# monoblink_wifi.net
KiCad netlist of a schematic drawn in EAGLE
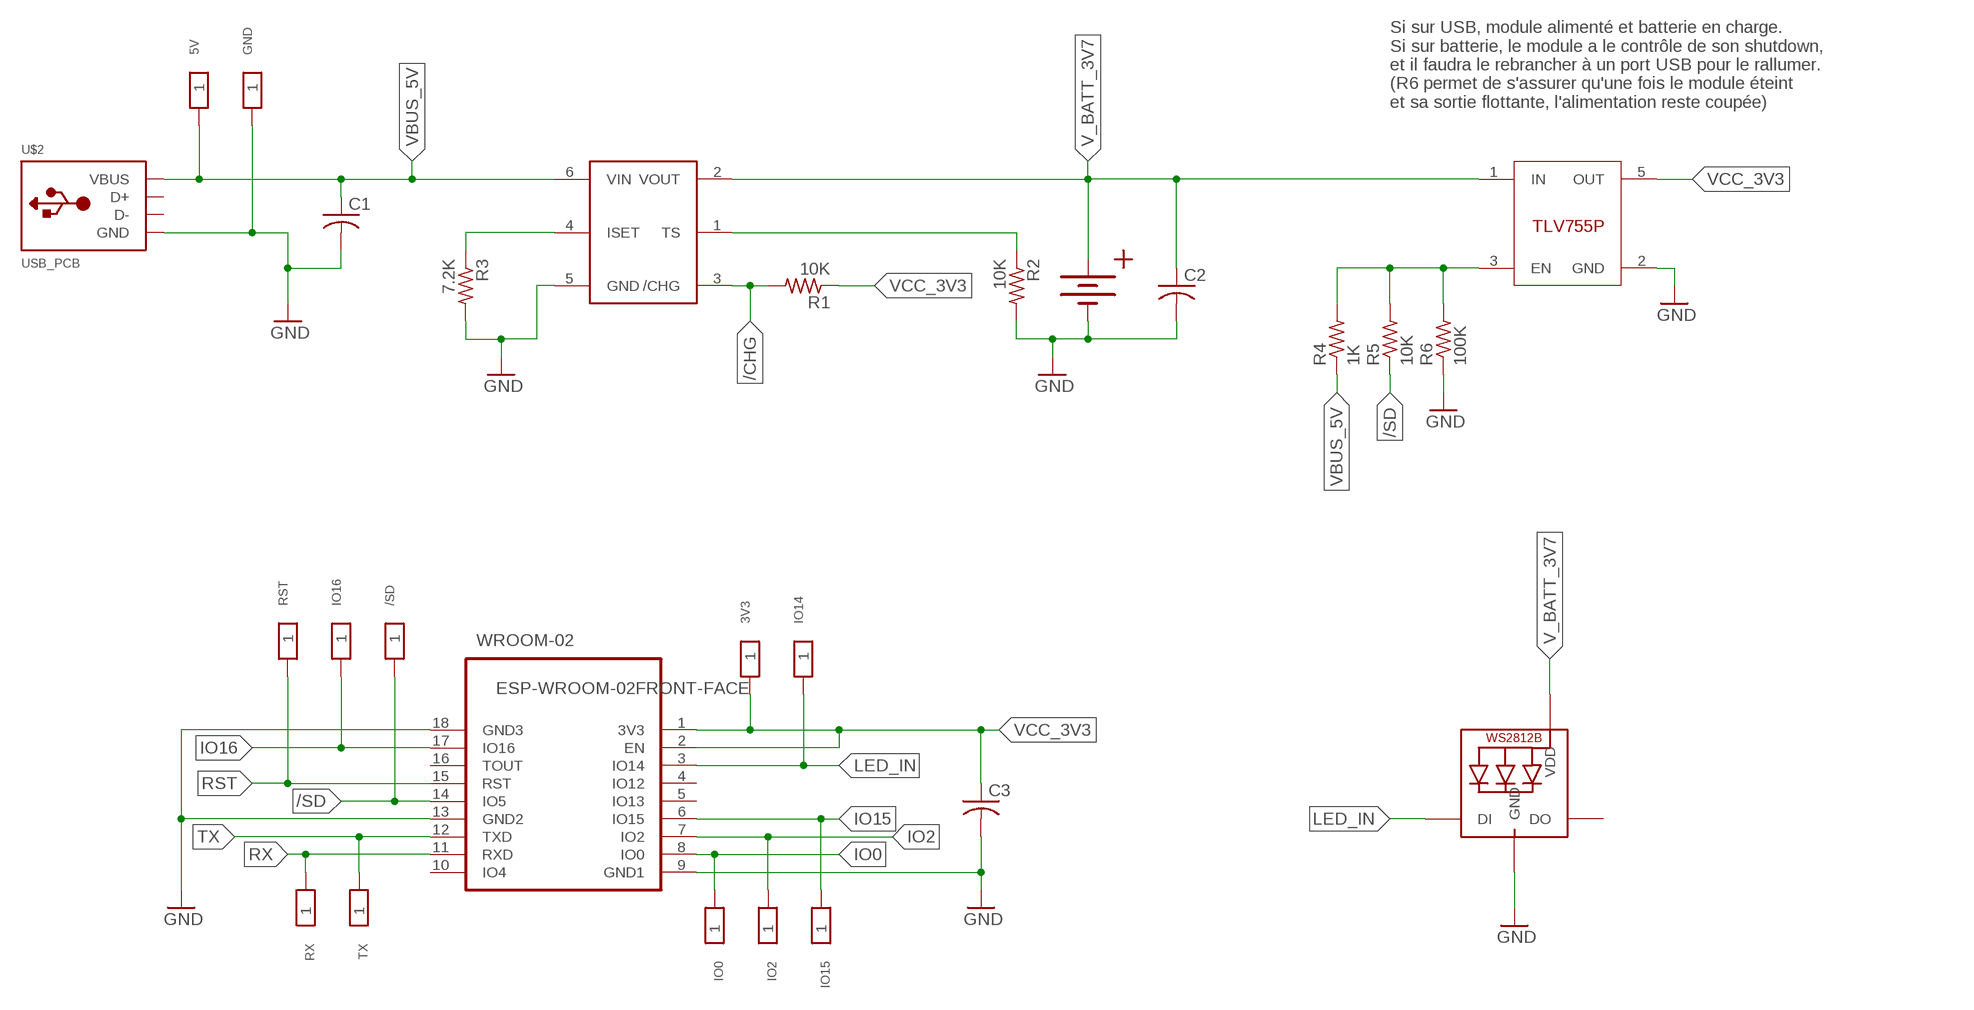
[diagram p0: schematic, sheet 1]

(export (version "E")
  (design (tool "Eeschema 10.0.6"))
  (components
    (comp (ref "/SD")
      (value "TESTPAD_PROG")
      (footprint "eagle-import:TP1.5MM")
      (libsource (lib "eagle-import") (part "TESTPAD_PROG"))
    )
    (comp (ref "3V3")
      (value "TESTPAD_PROG")
      (footprint "eagle-import:TP1.5MM")
      (libsource (lib "eagle-import") (part "TESTPAD_PROG"))
    )
    (comp (ref "5V")
      (value "TESTPAD_PROG")
      (footprint "eagle-import:TP1.5MM")
      (libsource (lib "eagle-import") (part "TESTPAD_PROG"))
    )
    (comp (ref "C1")
      (value "C-USC0603")
      (footprint "eagle-import:C0603")
      (libsource (lib "eagle-import") (part "C-USC0603"))
    )
    (comp (ref "C2")
      (value "C-USC0603")
      (footprint "eagle-import:C0603")
      (libsource (lib "eagle-import") (part "C-USC0603"))
    )
    (comp (ref "C3")
      (value "C-USC0603")
      (footprint "eagle-import:C0603")
      (libsource (lib "eagle-import") (part "C-USC0603"))
    )
    (comp (ref "CHG")
      (value "BQ21040")
      (footprint "eagle-import:SOT23-6")
      (libsource (lib "eagle-import") (part "BQ21040"))
    )
    (comp (ref "GND")
      (value "TESTPAD_PROG")
      (footprint "eagle-import:TP1.5MM")
      (libsource (lib "eagle-import") (part "TESTPAD_PROG"))
    )
    (comp (ref "IO0")
      (value "TESTPAD_PROG")
      (footprint "eagle-import:TP1.5MM")
      (libsource (lib "eagle-import") (part "TESTPAD_PROG"))
    )
    (comp (ref "IO2")
      (value "TESTPAD_PROG")
      (footprint "eagle-import:TP1.5MM")
      (libsource (lib "eagle-import") (part "TESTPAD_PROG"))
    )
    (comp (ref "IO14")
      (value "TESTPAD_PROG")
      (footprint "eagle-import:TP1.5MM")
      (libsource (lib "eagle-import") (part "TESTPAD_PROG"))
    )
    (comp (ref "IO15")
      (value "TESTPAD_PROG")
      (footprint "eagle-import:TP1.5MM")
      (libsource (lib "eagle-import") (part "TESTPAD_PROG"))
    )
    (comp (ref "IO16")
      (value "TESTPAD_PROG")
      (footprint "eagle-import:TP1.5MM")
      (libsource (lib "eagle-import") (part "TESTPAD_PROG"))
    )
    (comp (ref "LDO")
      (value "TLV755P")
      (footprint "eagle-import:SOT23-5")
      (libsource (lib "eagle-import") (part "TLV755P"))
    )
    (comp (ref "LED")
      (value "WS2812B5050")
      (footprint "eagle-import:WS2812B")
      (libsource (lib "eagle-import") (part "WS2812B5050"))
    )
    (comp (ref "R1")
      (value "10K")
      (footprint "eagle-import:R0603")
      (libsource (lib "eagle-import") (part "R-US_R0603"))
    )
    (comp (ref "R2")
      (value "10K")
      (footprint "eagle-import:R0603")
      (libsource (lib "eagle-import") (part "R-US_R0603"))
    )
    (comp (ref "R3")
      (value "7.2K")
      (footprint "eagle-import:R0603")
      (libsource (lib "eagle-import") (part "R-US_R0603"))
    )
    (comp (ref "R4")
      (value "1K")
      (footprint "eagle-import:R0603")
      (libsource (lib "eagle-import") (part "R-US_R0603"))
    )
    (comp (ref "R5")
      (value "10K")
      (footprint "eagle-import:R0603")
      (libsource (lib "eagle-import") (part "R-US_R0603"))
    )
    (comp (ref "R6")
      (value "100K")
      (footprint "eagle-import:R0603")
      (libsource (lib "eagle-import") (part "R-US_R0603"))
    )
    (comp (ref "RST")
      (value "TESTPAD_PROG")
      (footprint "eagle-import:TP1.5MM")
      (libsource (lib "eagle-import") (part "TESTPAD_PROG"))
    )
    (comp (ref "RX")
      (value "TESTPAD_PROG")
      (footprint "eagle-import:TP1.5MM")
      (libsource (lib "eagle-import") (part "TESTPAD_PROG"))
    )
    (comp (ref "TX")
      (value "TESTPAD_PROG")
      (footprint "eagle-import:TP1.5MM")
      (libsource (lib "eagle-import") (part "TESTPAD_PROG"))
    )
    (comp (ref "U$2")
      (value "USB_PCB")
      (footprint "eagle-import:USB_PADS")
      (libsource (lib "eagle-import") (part "USB_PCB"))
    )
    (comp (ref "U$5")
      (value "BATT")
      (footprint "eagle-import:BATT_CON")
      (libsource (lib "eagle-import") (part "BATT"))
    )
    (comp (ref "WROOM-02")
      (value "ESP-WROOM-02FRONT-FACE")
      (footprint "eagle-import:FRONT-FACE")
      (libsource (lib "eagle-import") (part "ESP-WROOM-02FRONT-FACE"))
    )
  )
  (nets
    (net (code "1") (name "GND") (class "Default")
      (node (ref "C1") (pin "2") (pinfunction "2_2") (pintype "passive"))
      (node (ref "C2") (pin "2") (pinfunction "2_2") (pintype "passive"))
      (node (ref "C3") (pin "2") (pinfunction "2_2") (pintype "passive"))
      (node (ref "CHG") (pin "5") (pinfunction "GND_5") (pintype "bidirectional"))
      (node (ref "GND") (pin "1") (pinfunction "1_1") (pintype "bidirectional"))
      (node (ref "LDO") (pin "2") (pinfunction "GND_2") (pintype "bidirectional"))
      (node (ref "LED") (pin "3-GND") (pinfunction "GND_3-GND") (pintype "power_in"))
      (node (ref "R2") (pin "2") (pinfunction "2_2") (pintype "passive"))
      (node (ref "R3") (pin "2") (pinfunction "2_2") (pintype "passive"))
      (node (ref "R6") (pin "1") (pinfunction "1_1") (pintype "passive"))
      (node (ref "U$2") (pin "GND") (pinfunction "GND_GND") (pintype "power_in"))
      (node (ref "U$5") (pin "V-") (pinfunction "-_V-") (pintype "power_in"))
      (node (ref "WROOM-02") (pin "13") (pinfunction "GND2_13") (pintype "power_in"))
      (node (ref "WROOM-02") (pin "18") (pinfunction "GND3_18") (pintype "power_in"))
      (node (ref "WROOM-02") (pin "9") (pinfunction "GND1_9") (pintype "power_in"))
    )
    (net (code "2") (name "IO0") (class "Default")
      (node (ref "IO0") (pin "1") (pinfunction "1_1") (pintype "bidirectional"))
      (node (ref "WROOM-02") (pin "8") (pinfunction "IO0_8") (pintype "bidirectional"))
    )
    (net (code "3") (name "IO2") (class "Default")
      (node (ref "IO2") (pin "1") (pinfunction "1_1") (pintype "bidirectional"))
      (node (ref "WROOM-02") (pin "7") (pinfunction "IO2_7") (pintype "bidirectional"))
    )
    (net (code "4") (name "IO15") (class "Default")
      (node (ref "IO15") (pin "1") (pinfunction "1_1") (pintype "bidirectional"))
      (node (ref "WROOM-02") (pin "6") (pinfunction "IO15_6") (pintype "bidirectional"))
    )
    (net (code "5") (name "IO16") (class "Default")
      (node (ref "IO16") (pin "1") (pinfunction "1_1") (pintype "bidirectional"))
      (node (ref "WROOM-02") (pin "17") (pinfunction "IO16_17") (pintype "bidirectional"))
    )
    (net (code "6") (name "LED_IN") (class "Default")
      (node (ref "IO14") (pin "1") (pinfunction "1_1") (pintype "bidirectional"))
      (node (ref "LED") (pin "4-DIN") (pinfunction "DI_4-DIN") (pintype "input"))
      (node (ref "WROOM-02") (pin "3") (pinfunction "IO14_3") (pintype "bidirectional"))
    )
    (net (code "7") (name "Net-(CHG-ISET)") (class "Default")
      (node (ref "CHG") (pin "4") (pinfunction "ISET_4") (pintype "bidirectional"))
      (node (ref "R3") (pin "1") (pinfunction "1_1") (pintype "passive"))
    )
    (net (code "8") (name "Net-(CHG-TS)") (class "Default")
      (node (ref "CHG") (pin "1") (pinfunction "TS_1") (pintype "bidirectional"))
      (node (ref "R2") (pin "1") (pinfunction "1_1") (pintype "passive"))
    )
    (net (code "9") (name "Net-(LDO-EN)") (class "Default")
      (node (ref "LDO") (pin "3") (pinfunction "EN_3") (pintype "bidirectional"))
      (node (ref "R4") (pin "2") (pinfunction "2_2") (pintype "passive"))
      (node (ref "R5") (pin "2") (pinfunction "2_2") (pintype "passive"))
      (node (ref "R6") (pin "2") (pinfunction "2_2") (pintype "passive"))
    )
    (net (code "10") (name "RST") (class "Default")
      (node (ref "RST") (pin "1") (pinfunction "1_1") (pintype "bidirectional"))
      (node (ref "WROOM-02") (pin "15") (pinfunction "RST_15") (pintype "bidirectional"))
    )
    (net (code "11") (name "RX") (class "Default")
      (node (ref "RX") (pin "1") (pinfunction "1_1") (pintype "bidirectional"))
      (node (ref "WROOM-02") (pin "11") (pinfunction "RXD_11") (pintype "bidirectional"))
    )
    (net (code "12") (name "TX") (class "Default")
      (node (ref "TX") (pin "1") (pinfunction "1_1") (pintype "bidirectional"))
      (node (ref "WROOM-02") (pin "12") (pinfunction "TXD_12") (pintype "bidirectional"))
    )
    (net (code "13") (name "VBUS_5V") (class "Default")
      (node (ref "5V") (pin "1") (pinfunction "1_1") (pintype "bidirectional"))
      (node (ref "C1") (pin "1") (pinfunction "1_1") (pintype "passive"))
      (node (ref "CHG") (pin "6") (pinfunction "VIN_6") (pintype "bidirectional"))
      (node (ref "R4") (pin "1") (pinfunction "1_1") (pintype "passive"))
      (node (ref "U$2") (pin "V_SUPPLY") (pinfunction "VBUS_V_SUPPLY") (pintype "power_in"))
    )
    (net (code "14") (name "VCC_3V3") (class "Default")
      (node (ref "3V3") (pin "1") (pinfunction "1_1") (pintype "bidirectional"))
      (node (ref "C3") (pin "1") (pinfunction "1_1") (pintype "passive"))
      (node (ref "LDO") (pin "5") (pinfunction "OUT_5") (pintype "bidirectional"))
      (node (ref "R1") (pin "1") (pinfunction "1_1") (pintype "passive"))
      (node (ref "WROOM-02") (pin "1") (pinfunction "3V3_1") (pintype "power_in"))
      (node (ref "WROOM-02") (pin "2") (pinfunction "EN_2") (pintype "bidirectional"))
    )
    (net (code "15") (name "V_BATT_3V7") (class "Default")
      (node (ref "C2") (pin "1") (pinfunction "1_1") (pintype "passive"))
      (node (ref "CHG") (pin "2") (pinfunction "VOUT_2") (pintype "bidirectional"))
      (node (ref "LDO") (pin "1") (pinfunction "IN_1") (pintype "bidirectional"))
      (node (ref "LED") (pin "1-VDD") (pinfunction "VDD_1-VDD") (pintype "power_in"))
      (node (ref "U$5") (pin "V+") (pinfunction "+_V+") (pintype "power_in"))
    )
    (net (code "16") (name "unconnected-(LED-DO-Pad2-DOUT)") (class "Default")
      (node (ref "LED") (pin "2-DOUT") (pinfunction "DO_2-DOUT") (pintype "output"))
    )
    (net (code "17") (name "unconnected-(U$2-PadD+)") (class "Default")
      (node (ref "U$2") (pin "D+") (pinfunction "D+_D+") (pintype "bidirectional"))
    )
    (net (code "18") (name "unconnected-(U$2-PadD-)") (class "Default")
      (node (ref "U$2") (pin "D-") (pinfunction "D-_D-") (pintype "bidirectional"))
    )
    (net (code "19") (name "unconnected-(WROOM-02-IO4-Pad10)") (class "Default")
      (node (ref "WROOM-02") (pin "10") (pinfunction "IO4_10") (pintype "bidirectional"))
    )
    (net (code "20") (name "unconnected-(WROOM-02-IO12-Pad4)") (class "Default")
      (node (ref "WROOM-02") (pin "4") (pinfunction "IO12_4") (pintype "bidirectional"))
    )
    (net (code "21") (name "unconnected-(WROOM-02-IO13-Pad5)") (class "Default")
      (node (ref "WROOM-02") (pin "5") (pinfunction "IO13_5") (pintype "bidirectional"))
    )
    (net (code "22") (name "unconnected-(WROOM-02-TOUT-Pad16)") (class "Default")
      (node (ref "WROOM-02") (pin "16") (pinfunction "TOUT_16") (pintype "bidirectional"))
    )
    (net (code "23") (name "{slash}CHG") (class "Default")
      (node (ref "CHG") (pin "3") (pinfunction "/CHG_3") (pintype "bidirectional"))
      (node (ref "R1") (pin "2") (pinfunction "2_2") (pintype "passive"))
    )
    (net (code "24") (name "{slash}SD") (class "Default")
      (node (ref "/SD") (pin "1") (pinfunction "1_1") (pintype "bidirectional"))
      (node (ref "R5") (pin "1") (pinfunction "1_1") (pintype "passive"))
      (node (ref "WROOM-02") (pin "14") (pinfunction "IO5_14") (pintype "open_collector"))
    )
  )
)
